# Connectors.net
KiCad netlist of a schematic drawn in Altium Designer
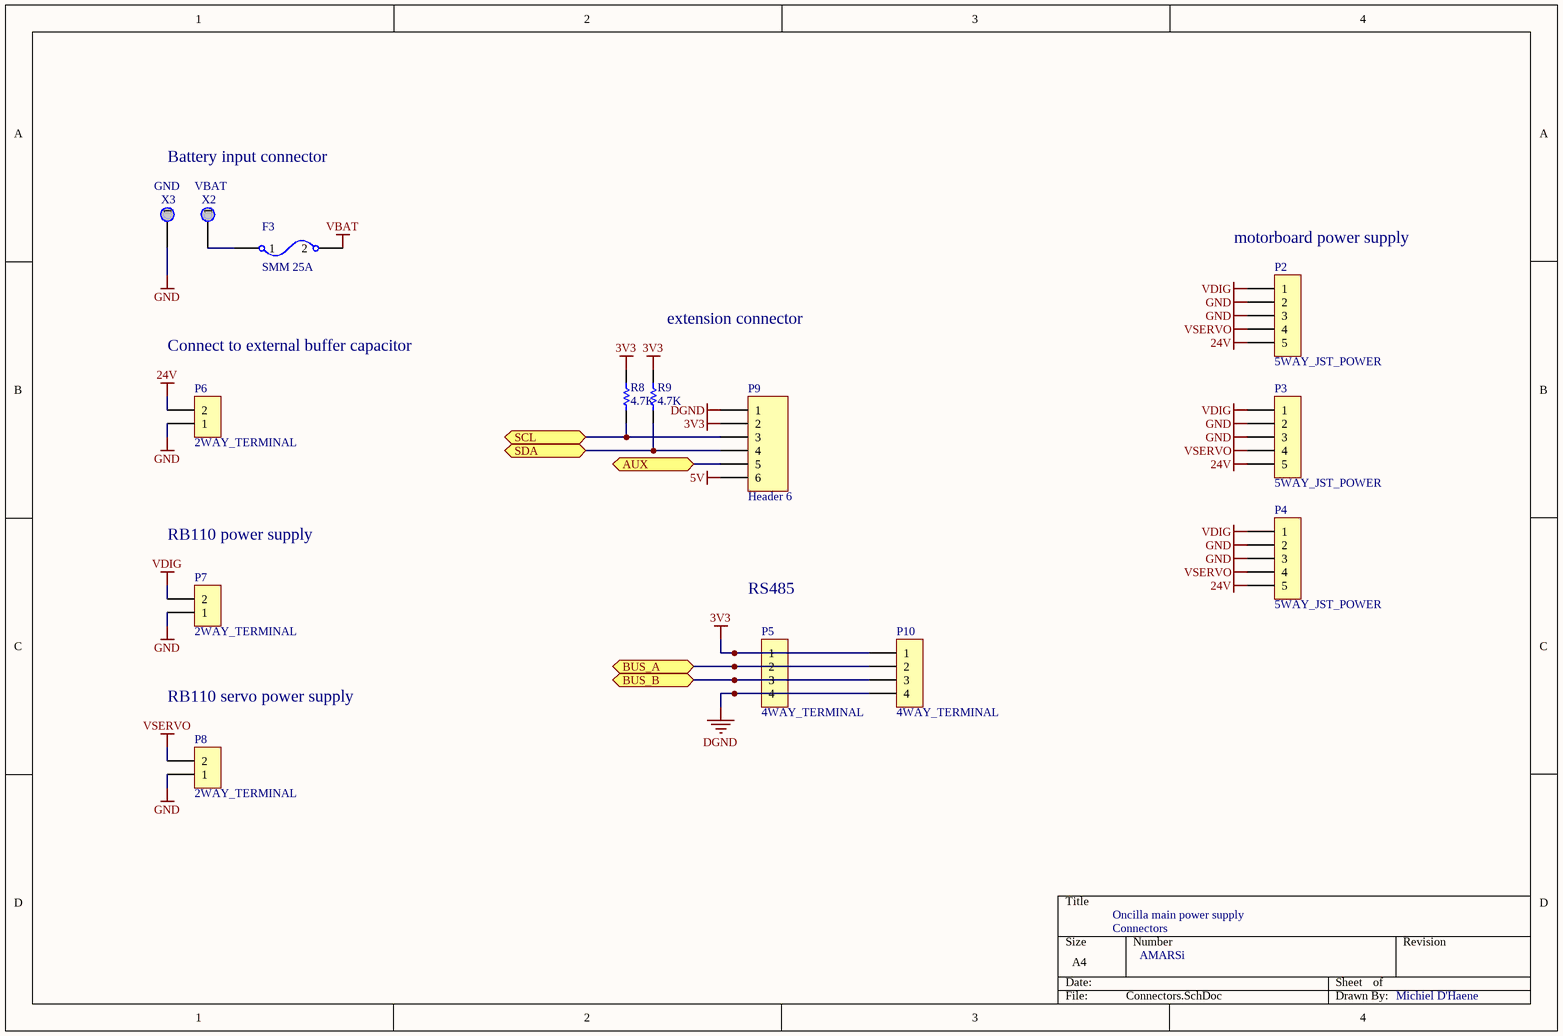
[diagram p0: Connectors.SchDoc]

(export (version "E")
  (design (tool "Eeschema 10.0.6"))
  (components
    (comp (ref "F3") (value "SMM 25A") (footprint "FUSE SMM") (libsource (lib "New_library") (part "fuse")))
    (comp (ref "P2")
      (value "5WAY_JST_POWER")
      (footprint "TERMINAL_5WAY_35")
      (libsource (lib "New_library") (part "5WAY_JST_POWER"))
    )
    (comp (ref "P3")
      (value "5WAY_JST_POWER")
      (footprint "TERMINAL_5WAY_35")
      (libsource (lib "New_library") (part "5WAY_JST_POWER"))
    )
    (comp (ref "P4")
      (value "5WAY_JST_POWER")
      (footprint "TERMINAL_5WAY_35")
      (libsource (lib "New_library") (part "5WAY_JST_POWER"))
    )
    (comp (ref "P5")
      (value "4WAY_TERMINAL")
      (footprint "MICROMATCH_4WAY_SE")
      (libsource (lib "New_library") (part "4WAY_TERMINAL"))
    )
    (comp (ref "P6")
      (value "2WAY_TERMINAL")
      (footprint "TYCO_2WAY_35MM")
      (libsource (lib "New_library") (part "2WAY_TERMINAL"))
    )
    (comp (ref "P7")
      (value "2WAY_TERMINAL")
      (footprint "TYCO_2WAY_35MM")
      (libsource (lib "New_library") (part "2WAY_TERMINAL"))
    )
    (comp (ref "P8")
      (value "2WAY_TERMINAL")
      (footprint "TYCO_2WAY_35MM")
      (libsource (lib "New_library") (part "2WAY_TERMINAL"))
    )
    (comp (ref "P9")
      (value "Header 6")
      (footprint "HDR1X6")
      (description "Header, 6-Pin")
      (fields (field (name "PUBLISHER") "Altium Limited"))
      (libsource (lib "Miscellaneous Connectors") (part "Header 6"))
    )
    (comp (ref "P10")
      (value "4WAY_TERMINAL")
      (footprint "MICROMATCH_4WAY_SE")
      (libsource (lib "New_library") (part "4WAY_TERMINAL"))
    )
    (comp (ref "R8")
      (value "4.7K")
      (footprint "RESC1608L")
      (description "Semiconductor Resistor")
      (fields (field (name "Comment") "4.7k") (field (name "PUBLISHER") "Altium Limited"))
      (libsource (lib "Miscellaneous Devices") (part "Res Semi"))
    )
    (comp (ref "R9")
      (value "4.7K")
      (footprint "RESC1608L")
      (description "Semiconductor Resistor")
      (fields (field (name "Comment") "4.7k") (field (name "PUBLISHER") "Altium Limited"))
      (libsource (lib "Miscellaneous Devices") (part "Res Semi"))
    )
    (comp (ref "X2")
      (value "VBAT")
      (footprint "TESTPIN 2MM")
      (libsource (lib "New_library") (part "1WAY_TERMINAL"))
    )
    (comp (ref "X3")
      (value "GND")
      (footprint "TESTPIN 2MM")
      (libsource (lib "New_library") (part "1WAY_TERMINAL"))
    )
  )
  (nets
    (net (code "1") (name "/AUX") (class "Default")
      (node (ref "P9") (pin "5") (pinfunction "5_5") (pintype "passive"))
    )
    (net (code "2") (name "/BUS_A") (class "Default")
      (node (ref "P10") (pin "2") (pinfunction "2_2") (pintype "passive"))
      (node (ref "P5") (pin "2") (pinfunction "2_2") (pintype "passive"))
    )
    (net (code "3") (name "/BUS_B") (class "Default")
      (node (ref "P10") (pin "3") (pinfunction "3_3") (pintype "passive"))
      (node (ref "P5") (pin "3") (pinfunction "3_3") (pintype "passive"))
    )
    (net (code "4") (name "/SCL") (class "Default")
      (node (ref "P9") (pin "3") (pinfunction "3_3") (pintype "passive"))
      (node (ref "R8") (pin "1") (pinfunction "1_1") (pintype "passive"))
    )
    (net (code "5") (name "/SDA") (class "Default")
      (node (ref "P9") (pin "4") (pinfunction "4_4") (pintype "passive"))
      (node (ref "R9") (pin "1") (pinfunction "1_1") (pintype "passive"))
    )
    (net (code "6") (name "3V3") (class "Default")
      (node (ref "P10") (pin "1") (pinfunction "1_1") (pintype "passive"))
      (node (ref "P5") (pin "1") (pinfunction "1_1") (pintype "passive"))
      (node (ref "P9") (pin "2") (pinfunction "2_2") (pintype "passive"))
      (node (ref "R8") (pin "2") (pinfunction "2_2") (pintype "passive"))
      (node (ref "R9") (pin "2") (pinfunction "2_2") (pintype "passive"))
    )
    (net (code "7") (name "5V") (class "Default")
      (node (ref "P9") (pin "6") (pinfunction "6_6") (pintype "passive"))
    )
    (net (code "8") (name "24V") (class "Default")
      (node (ref "P2") (pin "5") (pinfunction "5_5") (pintype "passive"))
      (node (ref "P3") (pin "5") (pinfunction "5_5") (pintype "passive"))
      (node (ref "P4") (pin "5") (pinfunction "5_5") (pintype "passive"))
      (node (ref "P6") (pin "2") (pinfunction "2_2") (pintype "passive"))
    )
    (net (code "9") (name "DGND") (class "Default")
      (node (ref "P10") (pin "4") (pinfunction "4_4") (pintype "passive"))
      (node (ref "P5") (pin "4") (pinfunction "4_4") (pintype "passive"))
      (node (ref "P9") (pin "1") (pinfunction "1_1") (pintype "passive"))
    )
    (net (code "10") (name "GND") (class "Default")
      (node (ref "P2") (pin "2") (pinfunction "2_2") (pintype "passive"))
      (node (ref "P2") (pin "3") (pinfunction "3_3") (pintype "passive"))
      (node (ref "P3") (pin "2") (pinfunction "2_2") (pintype "passive"))
      (node (ref "P3") (pin "3") (pinfunction "3_3") (pintype "passive"))
      (node (ref "P4") (pin "2") (pinfunction "2_2") (pintype "passive"))
      (node (ref "P4") (pin "3") (pinfunction "3_3") (pintype "passive"))
      (node (ref "P6") (pin "1") (pinfunction "1_1") (pintype "passive"))
      (node (ref "P7") (pin "1") (pinfunction "1_1") (pintype "passive"))
      (node (ref "P8") (pin "1") (pinfunction "1_1") (pintype "passive"))
      (node (ref "X3") (pin "1") (pinfunction "1_1") (pintype "passive"))
    )
    (net (code "11") (name "Net-(F3-Pad1)") (class "Default")
      (node (ref "F3") (pin "1") (pinfunction "1_1") (pintype "passive"))
      (node (ref "X2") (pin "1") (pinfunction "1_1") (pintype "passive"))
    )
    (net (code "12") (name "VBAT") (class "Default")
      (node (ref "F3") (pin "2") (pinfunction "2_2") (pintype "passive"))
    )
    (net (code "13") (name "VDIG") (class "Default")
      (node (ref "P2") (pin "1") (pinfunction "1_1") (pintype "passive"))
      (node (ref "P3") (pin "1") (pinfunction "1_1") (pintype "passive"))
      (node (ref "P4") (pin "1") (pinfunction "1_1") (pintype "passive"))
      (node (ref "P7") (pin "2") (pinfunction "2_2") (pintype "passive"))
    )
    (net (code "14") (name "VSERVO") (class "Default")
      (node (ref "P2") (pin "4") (pinfunction "4_4") (pintype "passive"))
      (node (ref "P3") (pin "4") (pinfunction "4_4") (pintype "passive"))
      (node (ref "P4") (pin "4") (pinfunction "4_4") (pintype "passive"))
      (node (ref "P8") (pin "2") (pinfunction "2_2") (pintype "passive"))
    )
  )
)
